# eduino_wifi_rev3.net
KiCad netlist of a schematic drawn in EAGLE
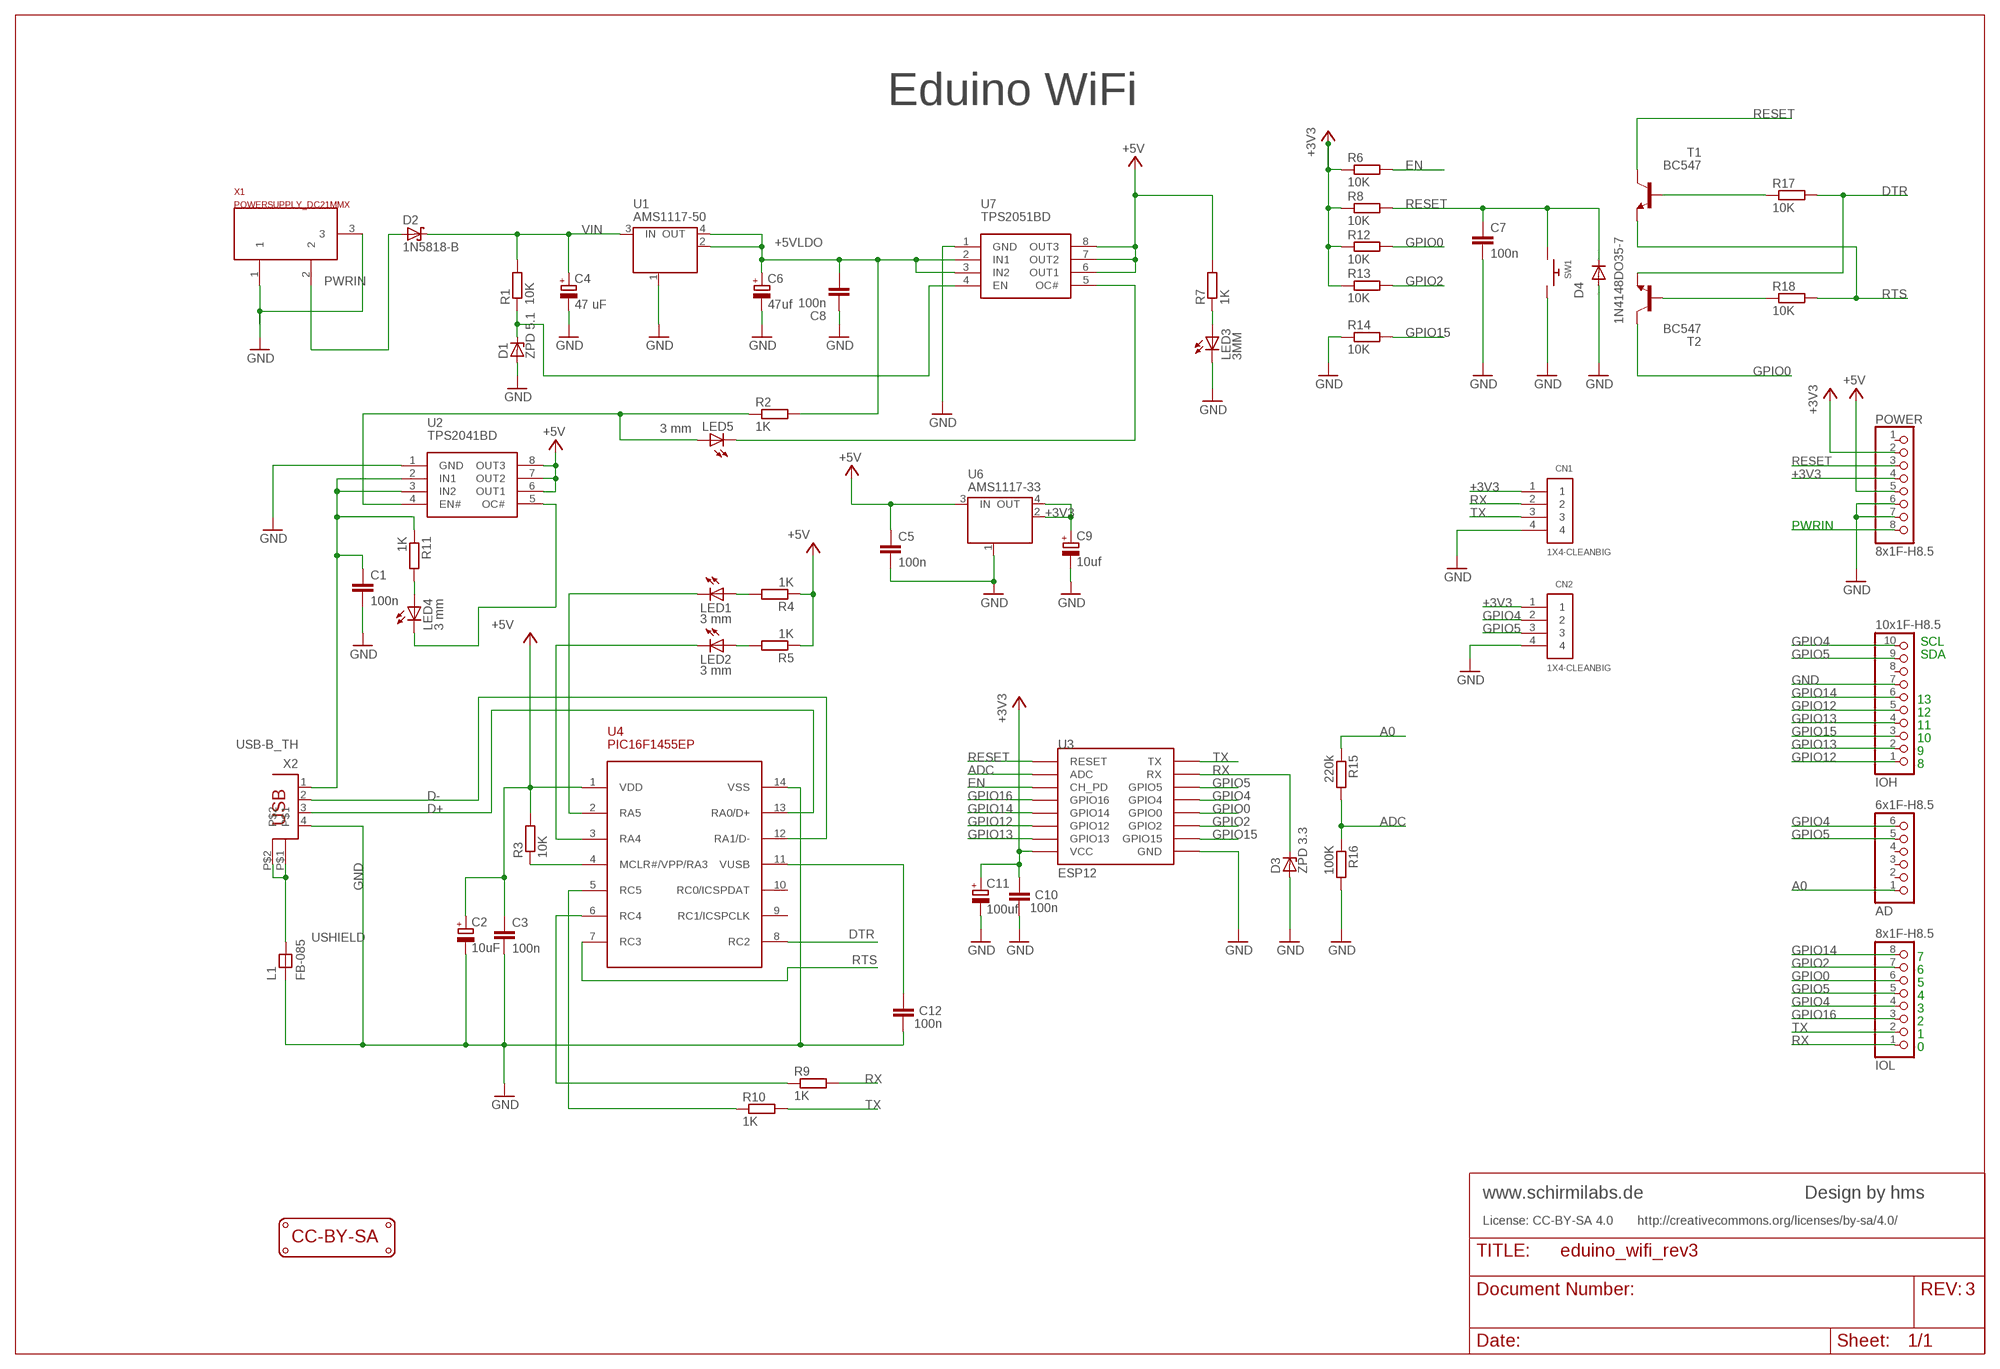
[diagram p0: schematic, sheet 1]

(export (version "E")
  (design (tool "Eeschema 10.0.6"))
  (components
    (comp (ref "AD")
      (value "6x1F-H8.5")
      (footprint "eagle-import:1X06")
      (libsource (lib "eagle-import") (part "PINHD-1X6"))
    )
    (comp (ref "C1")
      (value "100n")
      (footprint "eagle-import:C025-024X044")
      (libsource (lib "eagle-import") (part "C-EU025-024X044"))
    )
    (comp (ref "C2")
      (value "10uF")
      (footprint "eagle-import:E2-5")
      (libsource (lib "eagle-import") (part "CPOL-EUE2-5"))
    )
    (comp (ref "C3")
      (value "100n")
      (footprint "eagle-import:C025-024X044")
      (libsource (lib "eagle-import") (part "C-EU025-024X044"))
    )
    (comp (ref "C4")
      (value "47 uF")
      (footprint "eagle-import:E2-5")
      (libsource (lib "eagle-import") (part "CPOL-EUE2-5"))
    )
    (comp (ref "C5")
      (value "100n")
      (footprint "eagle-import:C025-024X044")
      (libsource (lib "eagle-import") (part "C-EU025-024X044"))
    )
    (comp (ref "C6")
      (value "47uf")
      (footprint "eagle-import:E2-5")
      (libsource (lib "eagle-import") (part "CPOL-EUE2-5"))
    )
    (comp (ref "C7")
      (value "100n")
      (footprint "eagle-import:C025-024X044")
      (libsource (lib "eagle-import") (part "C-EU025-024X044"))
    )
    (comp (ref "C8")
      (value "100n")
      (footprint "eagle-import:C0.1PTH")
      (libsource (lib "eagle-import") (part "CAPACITOR_NPOL-PTH_0.1{dblquote}"))
    )
    (comp (ref "C9")
      (value "10uf")
      (footprint "eagle-import:E2-5")
      (libsource (lib "eagle-import") (part "CPOL-EUE2-5"))
    )
    (comp (ref "C10")
      (value "100n")
      (footprint "eagle-import:C0.1PTH")
      (libsource (lib "eagle-import") (part "CAPACITOR_NPOL-PTH_0.1{dblquote}"))
    )
    (comp (ref "C11")
      (value "100uf")
      (footprint "eagle-import:E2-5")
      (libsource (lib "eagle-import") (part "CPOL-EUE2-5"))
    )
    (comp (ref "C12")
      (value "100n")
      (footprint "eagle-import:C0.1PTH")
      (libsource (lib "eagle-import") (part "CAPACITOR_NPOL-PTH_0.1{dblquote}"))
    )
    (comp (ref "CN1")
      (value "1X4-CLEANBIG")
      (footprint "eagle-import:1X04-CLEANBIG")
      (libsource (lib "eagle-import") (part "1X4-CLEANBIG"))
    )
    (comp (ref "CN2")
      (value "1X4-CLEANBIG")
      (footprint "eagle-import:1X04-CLEANBIG")
      (libsource (lib "eagle-import") (part "1X4-CLEANBIG"))
    )
    (comp (ref "D1")
      (value "ZPD 5.1")
      (footprint "eagle-import:DO35Z10")
      (libsource (lib "eagle-import") (part "ZENER-DIODEDO35Z10"))
    )
    (comp (ref "D2")
      (value "1N5818-B")
      (footprint "eagle-import:DO41-7.6")
      (libsource (lib "eagle-import") (part "1N5818-B"))
    )
    (comp (ref "D3")
      (value "ZPD 3.3")
      (footprint "eagle-import:DO35Z10")
      (libsource (lib "eagle-import") (part "ZPD"))
    )
    (comp (ref "D4")
      (value "1N4148DO35-7")
      (footprint "eagle-import:DO35-7")
      (libsource (lib "eagle-import") (part "1N4148DO35-7"))
    )
    (comp (ref "IOH")
      (value "10x1F-H8.5")
      (footprint "eagle-import:1X10")
      (libsource (lib "eagle-import") (part "PINHD-1X10_ARD"))
    )
    (comp (ref "IOL")
      (value "8x1F-H8.5")
      (footprint "eagle-import:1X08")
      (libsource (lib "eagle-import") (part "PINHD-1X8"))
    )
    (comp (ref "L1")
      (value "FB-085")
      (footprint "eagle-import:FB-085")
      (libsource (lib "eagle-import") (part "FB-085"))
    )
    (comp (ref "LED1")
      (value "3 mm")
      (footprint "eagle-import:LED-3MM")
      (libsource (lib "eagle-import") (part "LED-3MM"))
    )
    (comp (ref "LED2")
      (value "3 mm")
      (footprint "eagle-import:LED-3MM")
      (libsource (lib "eagle-import") (part "LED-3MM"))
    )
    (comp (ref "LED3")
      (value "3MM")
      (footprint "eagle-import:LED-3MM")
      (libsource (lib "eagle-import") (part "LED-3MM"))
    )
    (comp (ref "LED4")
      (value "3 mm")
      (footprint "eagle-import:LED-3MM")
      (libsource (lib "eagle-import") (part "LED-3MM"))
    )
    (comp (ref "LED5")
      (value "3 mm")
      (footprint "eagle-import:LED-3MM")
      (libsource (lib "eagle-import") (part "LED-3MM"))
    )
    (comp (ref "LOGO1")
      (value "LOGO_CC-BY-SA")
      (footprint "eagle-import:LOGO_CC-BY-SA")
      (libsource (lib "eagle-import") (part "LOGO_CC-BY-SA"))
    )
    (comp (ref "POWER")
      (value "8x1F-H8.5")
      (footprint "eagle-import:1X08")
      (libsource (lib "eagle-import") (part "PINHD-1X8"))
    )
    (comp (ref "R1")
      (value "10K")
      (footprint "eagle-import:RTH025W")
      (libsource (lib "eagle-import") (part "RESISTOR-PTH-0.4"))
    )
    (comp (ref "R2")
      (value "1K")
      (footprint "eagle-import:RTH025W")
      (libsource (lib "eagle-import") (part "RESISTOR-PTH-0.4"))
    )
    (comp (ref "R3")
      (value "10K")
      (footprint "eagle-import:0207_10")
      (libsource (lib "eagle-import") (part "R-EU_0207/10"))
    )
    (comp (ref "R4")
      (value "1K")
      (footprint "eagle-import:RTH025W")
      (libsource (lib "eagle-import") (part "RESISTOR-PTH-0.4"))
    )
    (comp (ref "R5")
      (value "1K")
      (footprint "eagle-import:RTH025W")
      (libsource (lib "eagle-import") (part "RESISTOR-PTH-0.4"))
    )
    (comp (ref "R6")
      (value "10K")
      (footprint "eagle-import:RTH025W")
      (libsource (lib "eagle-import") (part "RESISTOR-PTH-0.4"))
    )
    (comp (ref "R7")
      (value "1K")
      (footprint "eagle-import:RTH025W")
      (libsource (lib "eagle-import") (part "RESISTOR-PTH-0.4"))
    )
    (comp (ref "R8")
      (value "10K")
      (footprint "eagle-import:RTH025W")
      (libsource (lib "eagle-import") (part "RESISTOR-PTH-0.4"))
    )
    (comp (ref "R9")
      (value "1K")
      (footprint "eagle-import:0207_10")
      (libsource (lib "eagle-import") (part "R-EU_0207/10"))
    )
    (comp (ref "R10")
      (value "1K")
      (footprint "eagle-import:0207_10")
      (libsource (lib "eagle-import") (part "R-EU_0207/10"))
    )
    (comp (ref "R11")
      (value "1K")
      (footprint "eagle-import:RTH025W")
      (libsource (lib "eagle-import") (part "RESISTOR-PTH-0.4"))
    )
    (comp (ref "R12")
      (value "10K")
      (footprint "eagle-import:RTH025W")
      (libsource (lib "eagle-import") (part "RESISTOR-PTH-0.4"))
    )
    (comp (ref "R13")
      (value "10K")
      (footprint "eagle-import:RTH025W")
      (libsource (lib "eagle-import") (part "RESISTOR-PTH-0.4"))
    )
    (comp (ref "R14")
      (value "10K")
      (footprint "eagle-import:RTH025W")
      (libsource (lib "eagle-import") (part "RESISTOR-PTH-0.4"))
    )
    (comp (ref "R15")
      (value "220k")
      (footprint "eagle-import:RTH025W")
      (libsource (lib "eagle-import") (part "RESISTOR-PTH-0.4"))
    )
    (comp (ref "R16")
      (value "100K")
      (footprint "eagle-import:RTH025W")
      (libsource (lib "eagle-import") (part "RESISTOR-PTH-0.4"))
    )
    (comp (ref "R17")
      (value "10K")
      (footprint "eagle-import:RTH025W")
      (libsource (lib "eagle-import") (part "RESISTOR-PTH-0.4"))
    )
    (comp (ref "R18")
      (value "10K")
      (footprint "eagle-import:RTH025W")
      (libsource (lib "eagle-import") (part "RESISTOR-PTH-0.4"))
    )
    (comp (ref "SW1")
      (value "SWITCH_PUSHBUTTONEVQ-PE")
      (footprint "eagle-import:TACT_PANA-EVQ")
      (libsource (lib "eagle-import") (part "SWITCH_PUSHBUTTONEVQ-PE"))
    )
    (comp (ref "T1")
      (value "BC547")
      (footprint "eagle-import:TO92")
      (libsource (lib "eagle-import") (part "BC547"))
    )
    (comp (ref "T2")
      (value "BC547")
      (footprint "eagle-import:TO92")
      (libsource (lib "eagle-import") (part "BC547"))
    )
    (comp (ref "U1")
      (value "AMS1117-50")
      (footprint "eagle-import:SOT223")
      (libsource (lib "eagle-import") (part "MC33269ST-3.3T3"))
    )
    (comp (ref "U2")
      (value "TPS2041BD")
      (footprint "eagle-import:SOIC-8")
      (libsource (lib "eagle-import") (part "TPS2041BD"))
    )
    (comp (ref "U3")
      (value "ESP12")
      (footprint "eagle-import:ESP12-SMD")
      (libsource (lib "eagle-import") (part "ESP12SMD"))
    )
    (comp (ref "U4")
      (value "PIC16F1455EP")
      (footprint "eagle-import:DIL14")
      (libsource (lib "eagle-import") (part "PIC16F1455EP"))
    )
    (comp (ref "U6")
      (value "AMS1117-33")
      (footprint "eagle-import:SOT223")
      (libsource (lib "eagle-import") (part "MC33269ST-3.3T3"))
    )
    (comp (ref "U7")
      (value "TPS2051BD")
      (footprint "eagle-import:SOIC-8")
      (libsource (lib "eagle-import") (part "TPS2051BD"))
    )
    (comp (ref "X1")
      (value "POWERSUPPLY_DC21MMX")
      (footprint "eagle-import:POWERSUPPLY_DC-21MM")
      (libsource (lib "eagle-import") (part "POWERSUPPLY_DC21MMX"))
    )
    (comp (ref "X2")
      (value "USB-B_TH")
      (footprint "eagle-import:PN61729")
      (libsource (lib "eagle-import") (part "PN61729"))
    )
  )
  (nets
    (net (code "1") (name "+3V3") (class "Default")
      (node (ref "C10") (pin "2") (pinfunction "2_2") (pintype "passive"))
      (node (ref "C11") (pin "+") (pinfunction "+_+") (pintype "passive"))
      (node (ref "C9") (pin "+") (pinfunction "+_+") (pintype "passive"))
      (node (ref "CN1") (pin "1") (pinfunction "1_1") (pintype "bidirectional"))
      (node (ref "CN2") (pin "1") (pinfunction "1_1") (pintype "bidirectional"))
      (node (ref "POWER") (pin "2") (pinfunction "2_2") (pintype "passive"))
      (node (ref "POWER") (pin "4") (pinfunction "4_4") (pintype "passive"))
      (node (ref "R12") (pin "1") (pinfunction "1_1") (pintype "passive"))
      (node (ref "R13") (pin "1") (pinfunction "1_1") (pintype "passive"))
      (node (ref "R6") (pin "1") (pinfunction "1_1") (pintype "passive"))
      (node (ref "R8") (pin "1") (pinfunction "1_1") (pintype "passive"))
      (node (ref "U3") (pin "VCC") (pinfunction "VCC_VCC") (pintype "bidirectional"))
      (node (ref "U6") (pin "2") (pinfunction "OUT_2") (pintype "passive"))
      (node (ref "U6") (pin "4") (pinfunction "OUT_4") (pintype "passive"))
    )
    (net (code "2") (name "+5V") (class "Default")
      (node (ref "C2") (pin "+") (pinfunction "+_+") (pintype "passive"))
      (node (ref "C3") (pin "1") (pinfunction "1_1") (pintype "passive"))
      (node (ref "C5") (pin "1") (pinfunction "1_1") (pintype "passive"))
      (node (ref "POWER") (pin "5") (pinfunction "5_5") (pintype "passive"))
      (node (ref "R3") (pin "2") (pinfunction "2_2") (pintype "passive"))
      (node (ref "R4") (pin "1") (pinfunction "1_1") (pintype "passive"))
      (node (ref "R5") (pin "1") (pinfunction "1_1") (pintype "passive"))
      (node (ref "R7") (pin "2") (pinfunction "2_2") (pintype "passive"))
      (node (ref "U2") (pin "6") (pinfunction "OUT1_6") (pintype "bidirectional"))
      (node (ref "U2") (pin "7") (pinfunction "OUT2_7") (pintype "bidirectional"))
      (node (ref "U2") (pin "8") (pinfunction "OUT3_8") (pintype "bidirectional"))
      (node (ref "U4") (pin "1") (pinfunction "VDD_1") (pintype "power_in"))
      (node (ref "U6") (pin "3") (pinfunction "IN_3") (pintype "input"))
      (node (ref "U7") (pin "6") (pinfunction "OUT1_6") (pintype "bidirectional"))
      (node (ref "U7") (pin "7") (pinfunction "OUT2_7") (pintype "bidirectional"))
      (node (ref "U7") (pin "8") (pinfunction "OUT3_8") (pintype "bidirectional"))
    )
    (net (code "3") (name "/+5VLDO") (class "Default")
      (node (ref "C6") (pin "+") (pinfunction "+_+") (pintype "passive"))
      (node (ref "C8") (pin "2") (pinfunction "2_2") (pintype "passive"))
      (node (ref "R2") (pin "2") (pinfunction "2_2") (pintype "passive"))
      (node (ref "U1") (pin "2") (pinfunction "OUT_2") (pintype "passive"))
      (node (ref "U1") (pin "4") (pinfunction "OUT_4") (pintype "passive"))
      (node (ref "U7") (pin "2") (pinfunction "IN1_2") (pintype "bidirectional"))
      (node (ref "U7") (pin "3") (pinfunction "IN2_3") (pintype "bidirectional"))
    )
    (net (code "4") (name "/A0") (class "Default")
      (node (ref "AD") (pin "1") (pinfunction "1_1") (pintype "passive"))
      (node (ref "R15") (pin "1") (pinfunction "1_1") (pintype "passive"))
    )
    (net (code "5") (name "/ADC") (class "Default")
      (node (ref "R15") (pin "2") (pinfunction "2_2") (pintype "passive"))
      (node (ref "R16") (pin "1") (pinfunction "1_1") (pintype "passive"))
      (node (ref "U3") (pin "ADC") (pinfunction "ADC_ADC") (pintype "bidirectional"))
    )
    (net (code "6") (name "/D+") (class "Default")
      (node (ref "U4") (pin "13") (pinfunction "RA0/D+_13") (pintype "bidirectional"))
      (node (ref "X2") (pin "3") (pinfunction "3_3") (pintype "bidirectional"))
    )
    (net (code "7") (name "/D-") (class "Default")
      (node (ref "U4") (pin "12") (pinfunction "RA1/D-_12") (pintype "bidirectional"))
      (node (ref "X2") (pin "2") (pinfunction "2_2") (pintype "bidirectional"))
    )
    (net (code "8") (name "/DTR") (class "Default")
      (node (ref "R17") (pin "2") (pinfunction "2_2") (pintype "passive"))
      (node (ref "T2") (pin "1") (pinfunction "E_1") (pintype "passive"))
      (node (ref "U4") (pin "8") (pinfunction "RC2_8") (pintype "bidirectional"))
    )
    (net (code "9") (name "/EN") (class "Default")
      (node (ref "R6") (pin "2") (pinfunction "2_2") (pintype "passive"))
      (node (ref "U3") (pin "CH_PD") (pinfunction "CH_PD_CH_PD") (pintype "bidirectional"))
    )
    (net (code "10") (name "/GPIO0") (class "Default")
      (node (ref "IOL") (pin "6") (pinfunction "6_6") (pintype "passive"))
      (node (ref "R12") (pin "2") (pinfunction "2_2") (pintype "passive"))
      (node (ref "T2") (pin "3") (pinfunction "C_3") (pintype "passive"))
      (node (ref "U3") (pin "GPIO0") (pinfunction "GPIO0_GPIO0") (pintype "bidirectional"))
    )
    (net (code "11") (name "/GPIO2") (class "Default")
      (node (ref "IOL") (pin "7") (pinfunction "7_7") (pintype "passive"))
      (node (ref "R13") (pin "2") (pinfunction "2_2") (pintype "passive"))
      (node (ref "U3") (pin "GPIO2") (pinfunction "GPIO2_GPIO2") (pintype "bidirectional"))
    )
    (net (code "12") (name "/GPIO4") (class "Default")
      (node (ref "AD") (pin "6") (pinfunction "6_6") (pintype "passive"))
      (node (ref "CN2") (pin "2") (pinfunction "2_2") (pintype "bidirectional"))
      (node (ref "IOH") (pin "10") (pinfunction "10_10") (pintype "passive"))
      (node (ref "IOL") (pin "4") (pinfunction "4_4") (pintype "passive"))
      (node (ref "U3") (pin "GPIO4") (pinfunction "GPIO5_GPIO4") (pintype "bidirectional"))
    )
    (net (code "13") (name "/GPIO5") (class "Default")
      (node (ref "AD") (pin "5") (pinfunction "5_5") (pintype "passive"))
      (node (ref "CN2") (pin "3") (pinfunction "3_3") (pintype "bidirectional"))
      (node (ref "IOH") (pin "9") (pinfunction "9_9") (pintype "passive"))
      (node (ref "IOL") (pin "5") (pinfunction "5_5") (pintype "passive"))
      (node (ref "U3") (pin "GPIO5") (pinfunction "GPIO4_GPIO5") (pintype "bidirectional"))
    )
    (net (code "14") (name "/GPIO12") (class "Default")
      (node (ref "IOH") (pin "1") (pinfunction "1_1") (pintype "passive"))
      (node (ref "IOH") (pin "5") (pinfunction "5_5") (pintype "passive"))
      (node (ref "U3") (pin "GPIO12") (pinfunction "GPIO12_GPIO12") (pintype "bidirectional"))
    )
    (net (code "15") (name "/GPIO13") (class "Default")
      (node (ref "IOH") (pin "2") (pinfunction "2_2") (pintype "passive"))
      (node (ref "IOH") (pin "4") (pinfunction "4_4") (pintype "passive"))
      (node (ref "U3") (pin "GPIO13") (pinfunction "GPIO13_GPIO13") (pintype "bidirectional"))
    )
    (net (code "16") (name "/GPIO14") (class "Default")
      (node (ref "IOH") (pin "6") (pinfunction "6_6") (pintype "passive"))
      (node (ref "IOL") (pin "8") (pinfunction "8_8") (pintype "passive"))
      (node (ref "U3") (pin "GPIO14") (pinfunction "GPIO14_GPIO14") (pintype "bidirectional"))
    )
    (net (code "17") (name "/GPIO15") (class "Default")
      (node (ref "IOH") (pin "3") (pinfunction "3_3") (pintype "passive"))
      (node (ref "R14") (pin "2") (pinfunction "2_2") (pintype "passive"))
      (node (ref "U3") (pin "GPIO15") (pinfunction "GPIO15_GPIO15") (pintype "bidirectional"))
    )
    (net (code "18") (name "/GPIO16") (class "Default")
      (node (ref "IOL") (pin "3") (pinfunction "3_3") (pintype "passive"))
      (node (ref "U3") (pin "GPIO16") (pinfunction "GPIO16_GPIO16") (pintype "bidirectional"))
    )
    (net (code "19") (name "/PWRIN") (class "Default")
      (node (ref "D2") (pin "A") (pinfunction "A_A") (pintype "passive"))
      (node (ref "POWER") (pin "8") (pinfunction "8_8") (pintype "passive"))
      (node (ref "X1") (pin "2") (pinfunction "2_2") (pintype "power_in"))
    )
    (net (code "20") (name "/RESET") (class "Default")
      (node (ref "C7") (pin "1") (pinfunction "1_1") (pintype "passive"))
      (node (ref "D4") (pin "C") (pinfunction "C_C") (pintype "passive"))
      (node (ref "POWER") (pin "3") (pinfunction "3_3") (pintype "passive"))
      (node (ref "R8") (pin "2") (pinfunction "2_2") (pintype "passive"))
      (node (ref "SW1") (pin "P$1") (pinfunction "P$1_P$1") (pintype "passive"))
      (node (ref "T1") (pin "3") (pinfunction "C_3") (pintype "passive"))
      (node (ref "U3") (pin "RESET") (pinfunction "RESET_RESET") (pintype "bidirectional"))
    )
    (net (code "21") (name "/RTS") (class "Default")
      (node (ref "R18") (pin "2") (pinfunction "2_2") (pintype "passive"))
      (node (ref "T1") (pin "1") (pinfunction "E_1") (pintype "passive"))
      (node (ref "U4") (pin "7") (pinfunction "RC3_7") (pintype "bidirectional"))
    )
    (net (code "22") (name "/RX") (class "Default")
      (node (ref "CN1") (pin "2") (pinfunction "2_2") (pintype "bidirectional"))
      (node (ref "D3") (pin "C") (pinfunction "C_C") (pintype "passive"))
      (node (ref "IOL") (pin "1") (pinfunction "1_1") (pintype "passive"))
      (node (ref "R9") (pin "2") (pinfunction "2_2") (pintype "passive"))
      (node (ref "U3") (pin "RXD0") (pinfunction "RX_RXD0") (pintype "bidirectional"))
    )
    (net (code "23") (name "/TX") (class "Default")
      (node (ref "CN1") (pin "3") (pinfunction "3_3") (pintype "bidirectional"))
      (node (ref "IOL") (pin "2") (pinfunction "2_2") (pintype "passive"))
      (node (ref "R10") (pin "2") (pinfunction "2_2") (pintype "passive"))
      (node (ref "U3") (pin "TXD0") (pinfunction "TX_TXD0") (pintype "bidirectional"))
    )
    (net (code "24") (name "/USHIELD") (class "Default")
      (node (ref "L1") (pin "2") (pinfunction "2_2") (pintype "passive"))
      (node (ref "X2") (pin "P$1") (pinfunction "P$1_P$1") (pintype "bidirectional"))
      (node (ref "X2") (pin "P$2") (pinfunction "P$2_P$2") (pintype "bidirectional"))
    )
    (net (code "25") (name "/VIN") (class "Default")
      (node (ref "C4") (pin "+") (pinfunction "+_+") (pintype "passive"))
      (node (ref "D2") (pin "C") (pinfunction "C_C") (pintype "passive"))
      (node (ref "R1") (pin "2") (pinfunction "2_2") (pintype "passive"))
      (node (ref "U1") (pin "3") (pinfunction "IN_3") (pintype "input"))
    )
    (net (code "26") (name "GND") (class "Default")
      (node (ref "C1") (pin "2") (pinfunction "2_2") (pintype "passive"))
      (node (ref "C10") (pin "1") (pinfunction "1_1") (pintype "passive"))
      (node (ref "C11") (pin "-") (pinfunction "-_-") (pintype "passive"))
      (node (ref "C12") (pin "1") (pinfunction "1_1") (pintype "passive"))
      (node (ref "C2") (pin "-") (pinfunction "-_-") (pintype "passive"))
      (node (ref "C3") (pin "2") (pinfunction "2_2") (pintype "passive"))
      (node (ref "C4") (pin "-") (pinfunction "-_-") (pintype "passive"))
      (node (ref "C5") (pin "2") (pinfunction "2_2") (pintype "passive"))
      (node (ref "C6") (pin "-") (pinfunction "-_-") (pintype "passive"))
      (node (ref "C7") (pin "2") (pinfunction "2_2") (pintype "passive"))
      (node (ref "C8") (pin "1") (pinfunction "1_1") (pintype "passive"))
      (node (ref "C9") (pin "-") (pinfunction "-_-") (pintype "passive"))
      (node (ref "CN1") (pin "4") (pinfunction "4_4") (pintype "bidirectional"))
      (node (ref "CN2") (pin "4") (pinfunction "4_4") (pintype "bidirectional"))
      (node (ref "D1") (pin "A") (pinfunction "A_A") (pintype "passive"))
      (node (ref "D3") (pin "A") (pinfunction "A_A") (pintype "passive"))
      (node (ref "D4") (pin "A") (pinfunction "A_A") (pintype "passive"))
      (node (ref "IOH") (pin "7") (pinfunction "7_7") (pintype "passive"))
      (node (ref "L1") (pin "1") (pinfunction "1_1") (pintype "passive"))
      (node (ref "LED3") (pin "K") (pinfunction "C_K") (pintype "passive"))
      (node (ref "POWER") (pin "6") (pinfunction "6_6") (pintype "passive"))
      (node (ref "POWER") (pin "7") (pinfunction "7_7") (pintype "passive"))
      (node (ref "R14") (pin "1") (pinfunction "1_1") (pintype "passive"))
      (node (ref "R16") (pin "2") (pinfunction "2_2") (pintype "passive"))
      (node (ref "SW1") (pin "P$2") (pinfunction "P$2_P$2") (pintype "passive"))
      (node (ref "U1") (pin "1") (pinfunction "GND/ADJ_1") (pintype "input"))
      (node (ref "U2") (pin "1") (pinfunction "GND_1") (pintype "power_in"))
      (node (ref "U3") (pin "GND") (pinfunction "GND_GND") (pintype "bidirectional"))
      (node (ref "U4") (pin "14") (pinfunction "VSS_14") (pintype "power_in"))
      (node (ref "U6") (pin "1") (pinfunction "GND/ADJ_1") (pintype "input"))
      (node (ref "U7") (pin "1") (pinfunction "GND_1") (pintype "power_in"))
      (node (ref "X1") (pin "1") (pinfunction "1_1") (pintype "power_in"))
      (node (ref "X1") (pin "3") (pinfunction "3_3") (pintype "power_in"))
      (node (ref "X2") (pin "4") (pinfunction "4_4") (pintype "bidirectional"))
    )
    (net (code "27") (name "Net-(LED1-C)") (class "Default")
      (node (ref "LED1") (pin "K") (pinfunction "C_K") (pintype "passive"))
      (node (ref "U4") (pin "2") (pinfunction "RA5_2") (pintype "bidirectional"))
    )
    (net (code "28") (name "Net-(LED1-PadA)") (class "Default")
      (node (ref "LED1") (pin "A") (pinfunction "A_A") (pintype "passive"))
      (node (ref "R4") (pin "2") (pinfunction "2_2") (pintype "passive"))
    )
    (net (code "29") (name "Net-(LED2-C)") (class "Default")
      (node (ref "LED2") (pin "K") (pinfunction "C_K") (pintype "passive"))
      (node (ref "U4") (pin "3") (pinfunction "RA4_3") (pintype "bidirectional"))
    )
    (net (code "30") (name "Net-(LED2-PadA)") (class "Default")
      (node (ref "LED2") (pin "A") (pinfunction "A_A") (pintype "passive"))
      (node (ref "R5") (pin "2") (pinfunction "2_2") (pintype "passive"))
    )
    (net (code "31") (name "Net-(LED3-PadA)") (class "Default")
      (node (ref "LED3") (pin "A") (pinfunction "A_A") (pintype "passive"))
      (node (ref "R7") (pin "1") (pinfunction "1_1") (pintype "passive"))
    )
    (net (code "32") (name "Net-(LED4-C)") (class "Default")
      (node (ref "LED4") (pin "K") (pinfunction "C_K") (pintype "passive"))
      (node (ref "U2") (pin "5") (pinfunction "OC#_5") (pintype "bidirectional"))
    )
    (net (code "33") (name "Net-(LED4-PadA)") (class "Default")
      (node (ref "LED4") (pin "A") (pinfunction "A_A") (pintype "passive"))
      (node (ref "R11") (pin "2") (pinfunction "2_2") (pintype "passive"))
    )
    (net (code "34") (name "Net-(LED5-C)") (class "Default")
      (node (ref "LED5") (pin "K") (pinfunction "C_K") (pintype "passive"))
      (node (ref "U7") (pin "5") (pinfunction "OC#_5") (pintype "bidirectional"))
    )
    (net (code "35") (name "Net-(T1-B)") (class "Default")
      (node (ref "R17") (pin "1") (pinfunction "1_1") (pintype "passive"))
      (node (ref "T1") (pin "2") (pinfunction "B_2") (pintype "passive"))
    )
    (net (code "36") (name "Net-(T2-B)") (class "Default")
      (node (ref "R18") (pin "1") (pinfunction "1_1") (pintype "passive"))
      (node (ref "T2") (pin "2") (pinfunction "B_2") (pintype "passive"))
    )
    (net (code "37") (name "Net-(U2-EN#)") (class "Default")
      (node (ref "LED5") (pin "A") (pinfunction "A_A") (pintype "passive"))
      (node (ref "R2") (pin "1") (pinfunction "1_1") (pintype "passive"))
      (node (ref "U2") (pin "4") (pinfunction "EN#_4") (pintype "bidirectional"))
    )
    (net (code "38") (name "Net-(U2-IN1)") (class "Default")
      (node (ref "C1") (pin "1") (pinfunction "1_1") (pintype "passive"))
      (node (ref "R11") (pin "1") (pinfunction "1_1") (pintype "passive"))
      (node (ref "U2") (pin "2") (pinfunction "IN1_2") (pintype "bidirectional"))
      (node (ref "U2") (pin "3") (pinfunction "IN2_3") (pintype "bidirectional"))
      (node (ref "X2") (pin "1") (pinfunction "1_1") (pintype "bidirectional"))
    )
    (net (code "39") (name "Net-(U4-MCLR#{slash}VPP{slash}RA3)") (class "Default")
      (node (ref "R3") (pin "1") (pinfunction "1_1") (pintype "passive"))
      (node (ref "U4") (pin "4") (pinfunction "MCLR#/VPP/RA3_4") (pintype "bidirectional"))
    )
    (net (code "40") (name "Net-(U4-RC4)") (class "Default")
      (node (ref "R9") (pin "1") (pinfunction "1_1") (pintype "passive"))
      (node (ref "U4") (pin "6") (pinfunction "RC4_6") (pintype "bidirectional"))
    )
    (net (code "41") (name "Net-(U4-RC5)") (class "Default")
      (node (ref "R10") (pin "1") (pinfunction "1_1") (pintype "passive"))
      (node (ref "U4") (pin "5") (pinfunction "RC5_5") (pintype "bidirectional"))
    )
    (net (code "42") (name "Net-(U4-VUSB)") (class "Default")
      (node (ref "C12") (pin "2") (pinfunction "2_2") (pintype "passive"))
      (node (ref "U4") (pin "11") (pinfunction "VUSB_11") (pintype "bidirectional"))
    )
    (net (code "43") (name "Net-(U7-EN)") (class "Default")
      (node (ref "D1") (pin "C") (pinfunction "C_C") (pintype "passive"))
      (node (ref "R1") (pin "1") (pinfunction "1_1") (pintype "passive"))
      (node (ref "U7") (pin "4") (pinfunction "EN_4") (pintype "bidirectional"))
    )
    (net (code "44") (name "unconnected-(AD-Pad2)") (class "Default")
      (node (ref "AD") (pin "2") (pinfunction "2_2") (pintype "passive"))
    )
    (net (code "45") (name "unconnected-(AD-Pad3)") (class "Default")
      (node (ref "AD") (pin "3") (pinfunction "3_3") (pintype "passive"))
    )
    (net (code "46") (name "unconnected-(AD-Pad4)") (class "Default")
      (node (ref "AD") (pin "4") (pinfunction "4_4") (pintype "passive"))
    )
    (net (code "47") (name "unconnected-(IOH-Pad8)") (class "Default")
      (node (ref "IOH") (pin "8") (pinfunction "8_8") (pintype "passive"))
    )
    (net (code "48") (name "unconnected-(POWER-Pad1)") (class "Default")
      (node (ref "POWER") (pin "1") (pinfunction "1_1") (pintype "passive"))
    )
    (net (code "49") (name "unconnected-(U4-RC0{slash}ICSPDAT-Pad10)") (class "Default")
      (node (ref "U4") (pin "10") (pinfunction "RC0/ICSPDAT_10") (pintype "bidirectional"))
    )
    (net (code "50") (name "unconnected-(U4-RC1{slash}ICSPCLK-Pad9)") (class "Default")
      (node (ref "U4") (pin "9") (pinfunction "RC1/ICSPCLK_9") (pintype "bidirectional"))
    )
  )
)
